# 04pwr_pmic.net
KiCad netlist of a schematic drawn in Altium Designer
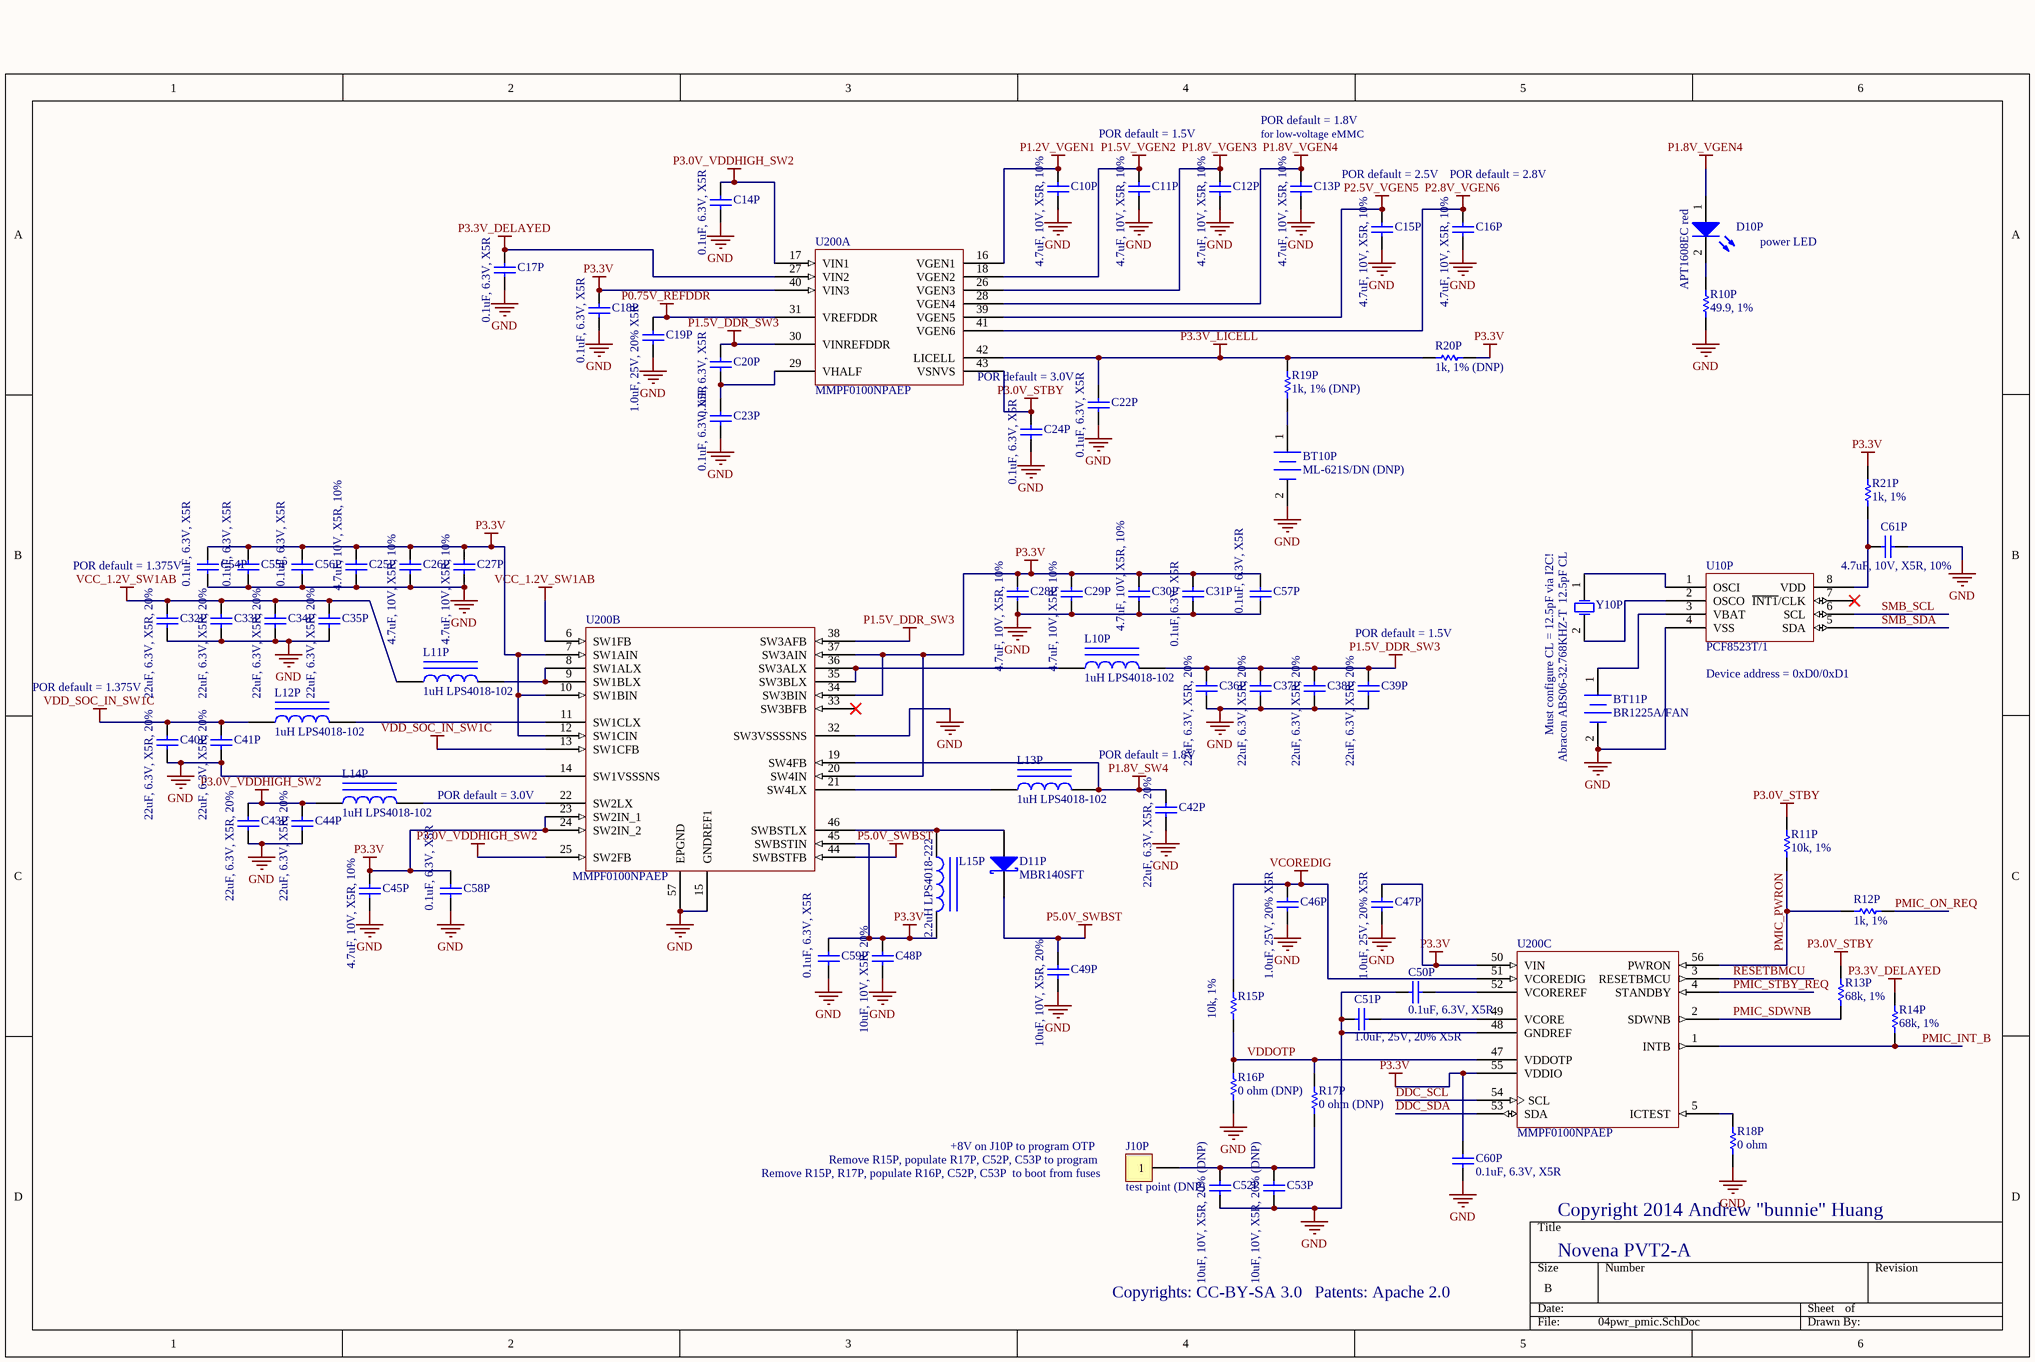
[diagram p0: 04pwr_pmic.SchDoc]

(export (version "E")
  (design (tool "Eeschema 10.0.6"))
  (components
    (comp (ref "BT10P")
      (value "ML-621S/DN (DNP)")
      (footprint "PAN_ML-621S-DN")
      (description "Panasonic Manganese Lithium Rechargeable battery")
      (fields (field (name "PUBLISHER") "Altium Limited"))
      (libsource (lib "Miscellaneous Devices") (part "Battery"))
    )
    (comp (ref "BT11P")
      (value "BR1225A/FAN")
      (footprint "BR1225A/FA")
      (description "Panasonic Manganese Lithium Rechargeable battery")
      (fields (field (name "PUBLISHER") "Altium Limited"))
      (libsource (lib "Miscellaneous Devices") (part "Battery"))
    )
    (comp (ref "C10P")
      (value "4.7uF, 10V, X5R, 10%")
      (footprint "CAPC1608N_HD")
      (description "Capacitor (Semiconductor SIM Model)")
      (fields (field (name "PUBLISHER") "Altium Limited"))
      (libsource (lib "Miscellaneous Devices") (part "Cap Semi"))
    )
    (comp (ref "C11P")
      (value "4.7uF, 10V, X5R, 10%")
      (footprint "CAPC1608N_HD")
      (description "Capacitor (Semiconductor SIM Model)")
      (fields (field (name "PUBLISHER") "Altium Limited"))
      (libsource (lib "Miscellaneous Devices") (part "Cap Semi"))
    )
    (comp (ref "C12P")
      (value "4.7uF, 10V, X5R, 10%")
      (footprint "CAPC1608N_HD")
      (description "Capacitor (Semiconductor SIM Model)")
      (fields (field (name "PUBLISHER") "Altium Limited"))
      (libsource (lib "Miscellaneous Devices") (part "Cap Semi"))
    )
    (comp (ref "C13P")
      (value "4.7uF, 10V, X5R, 10%")
      (footprint "CAPC1608N_HD")
      (description "Capacitor (Semiconductor SIM Model)")
      (fields (field (name "PUBLISHER") "Altium Limited"))
      (libsource (lib "Miscellaneous Devices") (part "Cap Semi"))
    )
    (comp (ref "C14P")
      (value "0.1uF, 6.3V, X5R")
      (footprint "CAPC0603N_B")
      (description "Capacitor (Semiconductor SIM Model)")
      (fields (field (name "PUBLISHER") "Altium Limited"))
      (libsource (lib "Miscellaneous Devices") (part "Cap Semi"))
    )
    (comp (ref "C15P")
      (value "4.7uF, 10V, X5R, 10%")
      (footprint "CAPC1608N_HD")
      (description "Capacitor (Semiconductor SIM Model)")
      (fields (field (name "PUBLISHER") "Altium Limited"))
      (libsource (lib "Miscellaneous Devices") (part "Cap Semi"))
    )
    (comp (ref "C16P")
      (value "4.7uF, 10V, X5R, 10%")
      (footprint "CAPC1608N_HD")
      (description "Capacitor (Semiconductor SIM Model)")
      (fields (field (name "PUBLISHER") "Altium Limited"))
      (libsource (lib "Miscellaneous Devices") (part "Cap Semi"))
    )
    (comp (ref "C17P")
      (value "0.1uF, 6.3V, X5R")
      (footprint "CAPC0603N_B")
      (description "Capacitor (Semiconductor SIM Model)")
      (fields (field (name "PUBLISHER") "Altium Limited"))
      (libsource (lib "Miscellaneous Devices") (part "Cap Semi"))
    )
    (comp (ref "C18P")
      (value "0.1uF, 6.3V, X5R")
      (footprint "CAPC0603N_B")
      (description "Capacitor (Semiconductor SIM Model)")
      (fields (field (name "PUBLISHER") "Altium Limited"))
      (libsource (lib "Miscellaneous Devices") (part "Cap Semi"))
    )
    (comp (ref "C19P")
      (value "1.0uF, 25V, 20% X5R")
      (footprint "CAPC1608N_HD")
      (description "Capacitor (Semiconductor SIM Model)")
      (fields (field (name "PUBLISHER") "Altium Limited"))
      (libsource (lib "Miscellaneous Devices") (part "Cap Semi"))
    )
    (comp (ref "C20P")
      (value "0.1uF, 6.3V, X5R")
      (footprint "CAPC0603N_B")
      (description "Capacitor (Semiconductor SIM Model)")
      (fields (field (name "PUBLISHER") "Altium Limited"))
      (libsource (lib "Miscellaneous Devices") (part "Cap Semi"))
    )
    (comp (ref "C22P")
      (value "0.1uF, 6.3V, X5R")
      (footprint "CAPC0603N_B")
      (description "Capacitor (Semiconductor SIM Model)")
      (fields (field (name "PUBLISHER") "Altium Limited"))
      (libsource (lib "Miscellaneous Devices") (part "Cap Semi"))
    )
    (comp (ref "C23P")
      (value "0.1uF, 6.3V, X5R")
      (footprint "CAPC0603N_B")
      (description "Capacitor (Semiconductor SIM Model)")
      (fields (field (name "PUBLISHER") "Altium Limited"))
      (libsource (lib "Miscellaneous Devices") (part "Cap Semi"))
    )
    (comp (ref "C24P")
      (value "0.1uF, 6.3V, X5R")
      (footprint "CAPC0603N_B")
      (description "Capacitor (Semiconductor SIM Model)")
      (fields (field (name "PUBLISHER") "Altium Limited"))
      (libsource (lib "Miscellaneous Devices") (part "Cap Semi"))
    )
    (comp (ref "C25P")
      (value "4.7uF, 10V, X5R, 10%")
      (footprint "CAPC1608N_HD")
      (description "Capacitor (Semiconductor SIM Model)")
      (fields (field (name "PUBLISHER") "Altium Limited"))
      (libsource (lib "Miscellaneous Devices") (part "Cap Semi"))
    )
    (comp (ref "C26P")
      (value "4.7uF, 10V, X5R, 10%")
      (footprint "CAPC1608N_HD")
      (description "Capacitor (Semiconductor SIM Model)")
      (fields (field (name "PUBLISHER") "Altium Limited"))
      (libsource (lib "Miscellaneous Devices") (part "Cap Semi"))
    )
    (comp (ref "C27P")
      (value "4.7uF, 10V, X5R, 10%")
      (footprint "CAPC1608N_HD")
      (description "Capacitor (Semiconductor SIM Model)")
      (fields (field (name "PUBLISHER") "Altium Limited"))
      (libsource (lib "Miscellaneous Devices") (part "Cap Semi"))
    )
    (comp (ref "C28P")
      (value "4.7uF, 10V, X5R, 10%")
      (footprint "CAPC1608N_HD")
      (description "Capacitor (Semiconductor SIM Model)")
      (fields (field (name "PUBLISHER") "Altium Limited"))
      (libsource (lib "Miscellaneous Devices") (part "Cap Semi"))
    )
    (comp (ref "C29P")
      (value "4.7uF, 10V, X5R, 10%")
      (footprint "CAPC1608N_HD")
      (description "Capacitor (Semiconductor SIM Model)")
      (fields (field (name "PUBLISHER") "Altium Limited"))
      (libsource (lib "Miscellaneous Devices") (part "Cap Semi"))
    )
    (comp (ref "C30P")
      (value "4.7uF, 10V, X5R, 10%")
      (footprint "CAPC1608N_HD")
      (description "Capacitor (Semiconductor SIM Model)")
      (fields (field (name "PUBLISHER") "Altium Limited"))
      (libsource (lib "Miscellaneous Devices") (part "Cap Semi"))
    )
    (comp (ref "C31P")
      (value "0.1uF, 6.3V, X5R")
      (footprint "CAPC0603N_B")
      (description "Capacitor (Semiconductor SIM Model)")
      (fields (field (name "PUBLISHER") "Altium Limited"))
      (libsource (lib "Miscellaneous Devices") (part "Cap Semi"))
    )
    (comp (ref "C32P")
      (value "22uF, 6.3V, X5R, 20%")
      (footprint "CAPC1608N_HD")
      (description "Capacitor (Semiconductor SIM Model)")
      (fields (field (name "PUBLISHER") "Altium Limited"))
      (libsource (lib "Miscellaneous Devices") (part "Cap Semi"))
    )
    (comp (ref "C33P")
      (value "22uF, 6.3V, X5R, 20%")
      (footprint "CAPC1608N_HD")
      (description "Capacitor (Semiconductor SIM Model)")
      (fields (field (name "PUBLISHER") "Altium Limited"))
      (libsource (lib "Miscellaneous Devices") (part "Cap Semi"))
    )
    (comp (ref "C34P")
      (value "22uF, 6.3V, X5R, 20%")
      (footprint "CAPC1608N_HD")
      (description "Capacitor (Semiconductor SIM Model)")
      (fields (field (name "PUBLISHER") "Altium Limited"))
      (libsource (lib "Miscellaneous Devices") (part "Cap Semi"))
    )
    (comp (ref "C35P")
      (value "22uF, 6.3V, X5R, 20%")
      (footprint "CAPC1608N_HD")
      (description "Capacitor (Semiconductor SIM Model)")
      (fields (field (name "PUBLISHER") "Altium Limited"))
      (libsource (lib "Miscellaneous Devices") (part "Cap Semi"))
    )
    (comp (ref "C36P")
      (value "22uF, 6.3V, X5R, 20%")
      (footprint "CAPC1608N_HD")
      (description "Capacitor (Semiconductor SIM Model)")
      (fields (field (name "PUBLISHER") "Altium Limited"))
      (libsource (lib "Miscellaneous Devices") (part "Cap Semi"))
    )
    (comp (ref "C37P")
      (value "22uF, 6.3V, X5R, 20%")
      (footprint "CAPC1608N_HD")
      (description "Capacitor (Semiconductor SIM Model)")
      (fields (field (name "PUBLISHER") "Altium Limited"))
      (libsource (lib "Miscellaneous Devices") (part "Cap Semi"))
    )
    (comp (ref "C38P")
      (value "22uF, 6.3V, X5R, 20%")
      (footprint "CAPC1608N_HD")
      (description "Capacitor (Semiconductor SIM Model)")
      (fields (field (name "PUBLISHER") "Altium Limited"))
      (libsource (lib "Miscellaneous Devices") (part "Cap Semi"))
    )
    (comp (ref "C39P")
      (value "22uF, 6.3V, X5R, 20%")
      (footprint "CAPC1608N_HD")
      (description "Capacitor (Semiconductor SIM Model)")
      (fields (field (name "PUBLISHER") "Altium Limited"))
      (libsource (lib "Miscellaneous Devices") (part "Cap Semi"))
    )
    (comp (ref "C40P")
      (value "22uF, 6.3V, X5R, 20%")
      (footprint "CAPC1608N_HD")
      (description "Capacitor (Semiconductor SIM Model)")
      (fields (field (name "PUBLISHER") "Altium Limited"))
      (libsource (lib "Miscellaneous Devices") (part "Cap Semi"))
    )
    (comp (ref "C41P")
      (value "22uF, 6.3V, X5R, 20%")
      (footprint "CAPC1608N_HD")
      (description "Capacitor (Semiconductor SIM Model)")
      (fields (field (name "PUBLISHER") "Altium Limited"))
      (libsource (lib "Miscellaneous Devices") (part "Cap Semi"))
    )
    (comp (ref "C42P")
      (value "22uF, 6.3V, X5R, 20%")
      (footprint "CAPC1608N_HD")
      (description "Capacitor (Semiconductor SIM Model)")
      (fields (field (name "PUBLISHER") "Altium Limited"))
      (libsource (lib "Miscellaneous Devices") (part "Cap Semi"))
    )
    (comp (ref "C43P")
      (value "22uF, 6.3V, X5R, 20%")
      (footprint "CAPC1608N_HD")
      (description "Capacitor (Semiconductor SIM Model)")
      (fields (field (name "PUBLISHER") "Altium Limited"))
      (libsource (lib "Miscellaneous Devices") (part "Cap Semi"))
    )
    (comp (ref "C44P")
      (value "22uF, 6.3V, X5R, 20%")
      (footprint "CAPC1608N_HD")
      (description "Capacitor (Semiconductor SIM Model)")
      (fields (field (name "PUBLISHER") "Altium Limited"))
      (libsource (lib "Miscellaneous Devices") (part "Cap Semi"))
    )
    (comp (ref "C45P")
      (value "4.7uF, 10V, X5R, 10%")
      (footprint "CAPC1608N_HD")
      (description "Capacitor (Semiconductor SIM Model)")
      (fields (field (name "PUBLISHER") "Altium Limited"))
      (libsource (lib "Miscellaneous Devices") (part "Cap Semi"))
    )
    (comp (ref "C46P")
      (value "1.0uF, 25V, 20% X5R")
      (footprint "CAPC1608N_HD")
      (description "Capacitor (Semiconductor SIM Model)")
      (fields (field (name "PUBLISHER") "Altium Limited"))
      (libsource (lib "Miscellaneous Devices") (part "Cap Semi"))
    )
    (comp (ref "C47P")
      (value "1.0uF, 25V, 20% X5R")
      (footprint "CAPC1608N_HD")
      (description "Capacitor (Semiconductor SIM Model)")
      (fields (field (name "PUBLISHER") "Altium Limited"))
      (libsource (lib "Miscellaneous Devices") (part "Cap Semi"))
    )
    (comp (ref "C48P")
      (value "10uF, 10V, X5R, 20%")
      (footprint "CAPC1608N")
      (description "Capacitor (Semiconductor SIM Model)")
      (fields (field (name "PUBLISHER") "Altium Limited"))
      (libsource (lib "Miscellaneous Devices") (part "Cap Semi"))
    )
    (comp (ref "C49P")
      (value "10uF, 10V, X5R, 20%")
      (footprint "CAPC1608N")
      (description "Capacitor (Semiconductor SIM Model)")
      (fields (field (name "PUBLISHER") "Altium Limited"))
      (libsource (lib "Miscellaneous Devices") (part "Cap Semi"))
    )
    (comp (ref "C50P")
      (value "0.1uF, 6.3V, X5R")
      (footprint "CAPC0603N_B")
      (description "Capacitor (Semiconductor SIM Model)")
      (fields (field (name "PUBLISHER") "Altium Limited"))
      (libsource (lib "Miscellaneous Devices") (part "Cap Semi"))
    )
    (comp (ref "C51P")
      (value "1.0uF, 25V, 20% X5R")
      (footprint "CAPC1608N_HD")
      (description "Capacitor (Semiconductor SIM Model)")
      (fields (field (name "PUBLISHER") "Altium Limited"))
      (libsource (lib "Miscellaneous Devices") (part "Cap Semi"))
    )
    (comp (ref "C52P")
      (value "10uF, 10V, X5R, 20% (DNP)")
      (footprint "CAPC1608N")
      (description "Capacitor (Semiconductor SIM Model)")
      (fields (field (name "PUBLISHER") "Altium Limited"))
      (libsource (lib "Miscellaneous Devices") (part "Cap Semi"))
    )
    (comp (ref "C53P")
      (value "10uF, 10V, X5R, 20% (DNP)")
      (footprint "CAPC1608N")
      (description "Capacitor (Semiconductor SIM Model)")
      (fields (field (name "PUBLISHER") "Altium Limited"))
      (libsource (lib "Miscellaneous Devices") (part "Cap Semi"))
    )
    (comp (ref "C54P")
      (value "0.1uF, 6.3V, X5R")
      (footprint "CAPC0603N_B")
      (description "Capacitor (Semiconductor SIM Model)")
      (fields (field (name "PUBLISHER") "Altium Limited"))
      (libsource (lib "Miscellaneous Devices") (part "Cap Semi"))
    )
    (comp (ref "C55P")
      (value "0.1uF, 6.3V, X5R")
      (footprint "CAPC0603N_B")
      (description "Capacitor (Semiconductor SIM Model)")
      (fields (field (name "PUBLISHER") "Altium Limited"))
      (libsource (lib "Miscellaneous Devices") (part "Cap Semi"))
    )
    (comp (ref "C56P")
      (value "0.1uF, 6.3V, X5R")
      (footprint "CAPC0603N_B")
      (description "Capacitor (Semiconductor SIM Model)")
      (fields (field (name "PUBLISHER") "Altium Limited"))
      (libsource (lib "Miscellaneous Devices") (part "Cap Semi"))
    )
    (comp (ref "C57P")
      (value "0.1uF, 6.3V, X5R")
      (footprint "CAPC0603N_B")
      (description "Capacitor (Semiconductor SIM Model)")
      (fields (field (name "PUBLISHER") "Altium Limited"))
      (libsource (lib "Miscellaneous Devices") (part "Cap Semi"))
    )
    (comp (ref "C58P")
      (value "0.1uF, 6.3V, X5R")
      (footprint "CAPC0603N_B")
      (description "Capacitor (Semiconductor SIM Model)")
      (fields (field (name "PUBLISHER") "Altium Limited"))
      (libsource (lib "Miscellaneous Devices") (part "Cap Semi"))
    )
    (comp (ref "C59P")
      (value "0.1uF, 6.3V, X5R")
      (footprint "CAPC0603N_B")
      (description "Capacitor (Semiconductor SIM Model)")
      (fields (field (name "PUBLISHER") "Altium Limited"))
      (libsource (lib "Miscellaneous Devices") (part "Cap Semi"))
    )
    (comp (ref "C60P")
      (value "0.1uF, 6.3V, X5R")
      (footprint "CAPC0603N_B")
      (description "Capacitor (Semiconductor SIM Model)")
      (fields (field (name "PUBLISHER") "Altium Limited"))
      (libsource (lib "Miscellaneous Devices") (part "Cap Semi"))
    )
    (comp (ref "C61P")
      (value "4.7uF, 10V, X5R, 10%")
      (footprint "CAPC1608N_HD")
      (description "Capacitor (Semiconductor SIM Model)")
      (fields (field (name "PUBLISHER") "Altium Limited"))
      (libsource (lib "Miscellaneous Devices") (part "Cap Semi"))
    )
    (comp (ref "D10P")
      (value "APT1608EC red")
      (footprint "CD1608-0603")
      (description "Typical RED, GREEN, YELLOW, AMBER GaAs LED")
      (fields (field (name "PUBLISHER") "Altium Limited"))
      (libsource (lib "Miscellaneous Devices") (part "LED2"))
    )
    (comp (ref "D11P")
      (value "MBR140SFT")
      (footprint "SOD123")
      (description "Schottky Diode")
      (fields (field (name "PUBLISHER") "Altium Limited"))
      (libsource (lib "Miscellaneous Devices") (part "D Schottky"))
    )
    (comp (ref "J10P")
      (value "test point (DNP)")
      (footprint "TP_SMT_38mil")
      (description "Connector")
      (libsource (lib "*") (part "CON1"))
    )
    (comp (ref "L10P")
      (value "1uH LPS4018-102")
      (footprint "COILCRAFT_LPS4018")
      (description "Magnetic-Core Inductor")
      (fields (field (name "PUBLISHER") "Altium Limited"))
      (libsource (lib "Miscellaneous Devices") (part "Inductor Iron"))
    )
    (comp (ref "L11P")
      (value "1uH LPS4018-102")
      (footprint "COILCRAFT_LPS4018")
      (description "Magnetic-Core Inductor")
      (fields (field (name "PUBLISHER") "Altium Limited"))
      (libsource (lib "Miscellaneous Devices") (part "Inductor Iron"))
    )
    (comp (ref "L12P")
      (value "1uH LPS4018-102")
      (footprint "COILCRAFT_LPS4018")
      (description "Magnetic-Core Inductor")
      (fields (field (name "PUBLISHER") "Altium Limited"))
      (libsource (lib "Miscellaneous Devices") (part "Inductor Iron"))
    )
    (comp (ref "L13P")
      (value "1uH LPS4018-102")
      (footprint "COILCRAFT_LPS4018")
      (description "Magnetic-Core Inductor")
      (fields (field (name "PUBLISHER") "Altium Limited"))
      (libsource (lib "Miscellaneous Devices") (part "Inductor Iron"))
    )
    (comp (ref "L14P")
      (value "1uH LPS4018-102")
      (footprint "COILCRAFT_LPS4018")
      (description "Magnetic-Core Inductor")
      (fields (field (name "PUBLISHER") "Altium Limited"))
      (libsource (lib "Miscellaneous Devices") (part "Inductor Iron"))
    )
    (comp (ref "L15P")
      (value "2.2uH LPS4018-222")
      (footprint "COILCRAFT_LPS4018")
      (description "Magnetic-Core Inductor")
      (fields (field (name "PUBLISHER") "Altium Limited"))
      (libsource (lib "Miscellaneous Devices") (part "Inductor Iron"))
    )
    (comp (ref "R10P")
      (value "49.9, 1%")
      (footprint "RESC1005N")
      (description "Resistor")
      (fields (field (name "PUBLISHER") "Altium Limited"))
      (libsource (lib "Miscellaneous Devices") (part "Res1"))
    )
    (comp (ref "R11P")
      (value "10k, 1%")
      (footprint "RESC1005N")
      (description "Resistor")
      (fields (field (name "PUBLISHER") "Altium Limited"))
      (libsource (lib "Miscellaneous Devices") (part "Res1"))
    )
    (comp (ref "R12P")
      (value "1k, 1%")
      (footprint "RESC1005N")
      (description "Resistor")
      (fields (field (name "PUBLISHER") "Altium Limited"))
      (libsource (lib "Miscellaneous Devices") (part "Res1"))
    )
    (comp (ref "R13P")
      (value "68k, 1%")
      (footprint "RESC1005N")
      (description "Resistor")
      (fields (field (name "PUBLISHER") "Altium Limited"))
      (libsource (lib "Miscellaneous Devices") (part "Res1"))
    )
    (comp (ref "R14P")
      (value "68k, 1%")
      (footprint "RESC1005N")
      (description "Resistor")
      (fields (field (name "PUBLISHER") "Altium Limited"))
      (libsource (lib "Miscellaneous Devices") (part "Res1"))
    )
    (comp (ref "R15P")
      (value "10k, 1%")
      (footprint "RESC1005N")
      (description "Resistor")
      (fields (field (name "PUBLISHER") "Altium Limited"))
      (libsource (lib "Miscellaneous Devices") (part "Res1"))
    )
    (comp (ref "R16P")
      (value "0 ohm (DNP)")
      (footprint "RESC1005N")
      (description "Resistor")
      (fields (field (name "PUBLISHER") "Altium Limited"))
      (libsource (lib "Miscellaneous Devices") (part "Res1"))
    )
    (comp (ref "R17P")
      (value "0 ohm (DNP)")
      (footprint "RESC1005N")
      (description "Resistor")
      (fields (field (name "PUBLISHER") "Altium Limited"))
      (libsource (lib "Miscellaneous Devices") (part "Res1"))
    )
    (comp (ref "R18P")
      (value "0 ohm")
      (footprint "RESC1005N")
      (description "Resistor")
      (fields (field (name "PUBLISHER") "Altium Limited"))
      (libsource (lib "Miscellaneous Devices") (part "Res1"))
    )
    (comp (ref "R19P")
      (value "1k, 1% (DNP)")
      (footprint "RESC1005N")
      (description "Resistor")
      (fields (field (name "PUBLISHER") "Altium Limited"))
      (libsource (lib "Miscellaneous Devices") (part "Res1"))
    )
    (comp (ref "R20P")
      (value "1k, 1% (DNP)")
      (footprint "RESC1005N")
      (description "Resistor")
      (fields (field (name "PUBLISHER") "Altium Limited"))
      (libsource (lib "Miscellaneous Devices") (part "Res1"))
    )
    (comp (ref "R21P")
      (value "1k, 1%")
      (footprint "RESC1005N")
      (description "Resistor")
      (fields (field (name "PUBLISHER") "Altium Limited"))
      (libsource (lib "Miscellaneous Devices") (part "Res1"))
    )
    (comp (ref "U10P")
      (value "PCF8523T/1")
      (footprint "SOIC127P600-8N")
      (description "RTC and calendar chip")
      (libsource (lib "commonsch") (part "PCF8523T/1"))
    )
    (comp (ref "U200")
      (value "MMPF0100NPAEP")
      (footprint "FREESCALE_QFN50P800X800X90-56N")
      (description "PMIC for i.MX6 series")
      (libsource (lib "commonsch") (part "PMPF0100NPEP"))
    )
    (comp (ref "Y10P")
      (value "Abracon ABS06-32.768KHZ-T  12.5pF CL")
      (footprint "ABS06")
      (description "Crystal Oscillator")
      (fields (field (name "PUBLISHER") "Altium Limited"))
      (libsource (lib "Miscellaneous Devices") (part "XTAL"))
    )
  )
  (nets
    (net (code "1") (name "/DDC_SCL") (class "Default")
      (node (ref "U200") (pin "54") (pinfunction "SCL_54") (pintype "input"))
    )
    (net (code "2") (name "/DDC_SDA") (class "Default")
      (node (ref "U200") (pin "53") (pinfunction "SDA_53") (pintype "bidirectional"))
    )
    (net (code "3") (name "/PMIC_INT_B") (class "Default")
      (node (ref "R14P") (pin "1") (pinfunction "1_1") (pintype "passive"))
      (node (ref "U200") (pin "1") (pinfunction "INTB_1") (pintype "output"))
    )
    (net (code "4") (name "/PMIC_ON_REQ") (class "Default")
      (node (ref "R12P") (pin "2") (pinfunction "2_2") (pintype "passive"))
    )
    (net (code "5") (name "/PMIC_PWRON") (class "Default")
      (node (ref "R11P") (pin "1") (pinfunction "1_1") (pintype "passive"))
      (node (ref "R12P") (pin "1") (pinfunction "1_1") (pintype "passive"))
      (node (ref "U200") (pin "56") (pinfunction "PWRON_56") (pintype "input"))
    )
    (net (code "6") (name "/PMIC_SDWNB") (class "Default")
      (node (ref "R13P") (pin "1") (pinfunction "1_1") (pintype "passive"))
      (node (ref "U200") (pin "2") (pinfunction "SDWNB_2") (pintype "output"))
    )
    (net (code "7") (name "/PMIC_STBY_REQ") (class "Default")
      (node (ref "U200") (pin "4") (pinfunction "STANDBY_4") (pintype "input"))
    )
    (net (code "8") (name "/RESETBMCU") (class "Default")
      (node (ref "U200") (pin "3") (pinfunction "RESETBMCU_3") (pintype "output"))
    )
    (net (code "9") (name "/SMB_SCL") (class "Default")
      (node (ref "U10P") (pin "6") (pinfunction "SCL_6") (pintype "bidirectional"))
    )
    (net (code "10") (name "/SMB_SDA") (class "Default")
      (node (ref "U10P") (pin "5") (pinfunction "SDA_5") (pintype "bidirectional"))
    )
    (net (code "11") (name "/VDDOTP") (class "Default")
      (node (ref "R15P") (pin "1") (pinfunction "1_1") (pintype "passive"))
      (node (ref "R16P") (pin "2") (pinfunction "2_2") (pintype "passive"))
      (node (ref "R17P") (pin "2") (pinfunction "2_2") (pintype "passive"))
      (node (ref "U200") (pin "47") (pinfunction "VDDOTP_47") (pintype "passive"))
    )
    (net (code "12") (name "GND") (class "Default")
      (node (ref "BT10P") (pin "2") (pinfunction "-_2") (pintype "passive"))
      (node (ref "BT11P") (pin "2") (pinfunction "-_2") (pintype "passive"))
      (node (ref "C10P") (pin "2") (pinfunction "2_2") (pintype "passive"))
      (node (ref "C11P") (pin "2") (pinfunction "2_2") (pintype "passive"))
      (node (ref "C12P") (pin "2") (pinfunction "2_2") (pintype "passive"))
      (node (ref "C13P") (pin "2") (pinfunction "2_2") (pintype "passive"))
      (node (ref "C14P") (pin "2") (pinfunction "2_2") (pintype "passive"))
      (node (ref "C15P") (pin "2") (pinfunction "2_2") (pintype "passive"))
      (node (ref "C16P") (pin "2") (pinfunction "2_2") (pintype "passive"))
      (node (ref "C17P") (pin "2") (pinfunction "2_2") (pintype "passive"))
      (node (ref "C18P") (pin "2") (pinfunction "2_2") (pintype "passive"))
      (node (ref "C19P") (pin "2") (pinfunction "2_2") (pintype "passive"))
      (node (ref "C22P") (pin "2") (pinfunction "2_2") (pintype "passive"))
      (node (ref "C23P") (pin "2") (pinfunction "2_2") (pintype "passive"))
      (node (ref "C24P") (pin "2") (pinfunction "2_2") (pintype "passive"))
      (node (ref "C25P") (pin "2") (pinfunction "2_2") (pintype "passive"))
      (node (ref "C26P") (pin "2") (pinfunction "2_2") (pintype "passive"))
      (node (ref "C27P") (pin "2") (pinfunction "2_2") (pintype "passive"))
      (node (ref "C28P") (pin "2") (pinfunction "2_2") (pintype "passive"))
      (node (ref "C29P") (pin "2") (pinfunction "2_2") (pintype "passive"))
      (node (ref "C30P") (pin "2") (pinfunction "2_2") (pintype "passive"))
      (node (ref "C31P") (pin "2") (pinfunction "2_2") (pintype "passive"))
      (node (ref "C32P") (pin "2") (pinfunction "2_2") (pintype "passive"))
      (node (ref "C33P") (pin "2") (pinfunction "2_2") (pintype "passive"))
      (node (ref "C34P") (pin "2") (pinfunction "2_2") (pintype "passive"))
      (node (ref "C35P") (pin "2") (pinfunction "2_2") (pintype "passive"))
      (node (ref "C36P") (pin "2") (pinfunction "2_2") (pintype "passive"))
      (node (ref "C37P") (pin "2") (pinfunction "2_2") (pintype "passive"))
      (node (ref "C38P") (pin "2") (pinfunction "2_2") (pintype "passive"))
      (node (ref "C39P") (pin "2") (pinfunction "2_2") (pintype "passive"))
      (node (ref "C40P") (pin "2") (pinfunction "2_2") (pintype "passive"))
      (node (ref "C41P") (pin "2") (pinfunction "2_2") (pintype "passive"))
      (node (ref "C42P") (pin "2") (pinfunction "2_2") (pintype "passive"))
      (node (ref "C43P") (pin "2") (pinfunction "2_2") (pintype "passive"))
      (node (ref "C44P") (pin "2") (pinfunction "2_2") (pintype "passive"))
      (node (ref "C45P") (pin "2") (pinfunction "2_2") (pintype "passive"))
      (node (ref "C46P") (pin "2") (pinfunction "2_2") (pintype "passive"))
      (node (ref "C47P") (pin "2") (pinfunction "2_2") (pintype "passive"))
      (node (ref "C48P") (pin "2") (pinfunction "2_2") (pintype "passive"))
      (node (ref "C49P") (pin "2") (pinfunction "2_2") (pintype "passive"))
      (node (ref "C50P") (pin "2") (pinfunction "2_2") (pintype "passive"))
      (node (ref "C51P") (pin "2") (pinfunction "2_2") (pintype "passive"))
      (node (ref "C52P") (pin "2") (pinfunction "2_2") (pintype "passive"))
      (node (ref "C53P") (pin "2") (pinfunction "2_2") (pintype "passive"))
      (node (ref "C54P") (pin "2") (pinfunction "2_2") (pintype "passive"))
      (node (ref "C55P") (pin "2") (pinfunction "2_2") (pintype "passive"))
      (node (ref "C56P") (pin "2") (pinfunction "2_2") (pintype "passive"))
      (node (ref "C57P") (pin "2") (pinfunction "2_2") (pintype "passive"))
      (node (ref "C58P") (pin "2") (pinfunction "2_2") (pintype "passive"))
      (node (ref "C59P") (pin "2") (pinfunction "2_2") (pintype "passive"))
      (node (ref "C60P") (pin "1") (pinfunction "1_1") (pintype "passive"))
      (node (ref "C61P") (pin "2") (pinfunction "2_2") (pintype "passive"))
      (node (ref "R10P") (pin "1") (pinfunction "1_1") (pintype "passive"))
      (node (ref "R16P") (pin "1") (pinfunction "1_1") (pintype "passive"))
      (node (ref "R18P") (pin "1") (pinfunction "1_1") (pintype "passive"))
      (node (ref "U10P") (pin "4") (pinfunction "VSS_4") (pintype "power_in"))
      (node (ref "U200") (pin "14") (pinfunction "SW1VSSSNS_14") (pintype "power_in"))
      (node (ref "U200") (pin "15") (pinfunction "GNDREF1_15") (pintype "power_in"))
      (node (ref "U200") (pin "32") (pinfunction "SW3VSSSSNS_32") (pintype "power_in"))
      (node (ref "U200") (pin "48") (pinfunction "GNDREF_48") (pintype "power_in"))
      (node (ref "U200") (pin "57") (pinfunction "EPGND_57") (pintype "power_in"))
    )
    (net (code "13") (name "Net-(BT10P-+)") (class "Default")
      (node (ref "BT10P") (pin "1") (pinfunction "+_1") (pintype "passive"))
      (node (ref "R19P") (pin "1") (pinfunction "1_1") (pintype "passive"))
    )
    (net (code "14") (name "Net-(BT11P-+)") (class "Default")
      (node (ref "BT11P") (pin "1") (pinfunction "+_1") (pintype "passive"))
      (node (ref "U10P") (pin "3") (pinfunction "VBAT_3") (pintype "power_in"))
    )
    (net (code "15") (name "Net-(C52P-Pad1)") (class "Default")
      (node (ref "C52P") (pin "1") (pinfunction "1_1") (pintype "passive"))
      (node (ref "C53P") (pin "1") (pinfunction "1_1") (pintype "passive"))
      (node (ref "J10P") (pin "1") (pinfunction "1_1") (pintype "passive"))
      (node (ref "R17P") (pin "1") (pinfunction "1_1") (pintype "passive"))
    )
    (net (code "16") (name "Net-(D10P-K)") (class "Default")
      (node (ref "D10P") (pin "2") (pinfunction "K_2") (pintype "passive"))
      (node (ref "R10P") (pin "2") (pinfunction "2_2") (pintype "passive"))
    )
    (net (code "17") (name "Net-(D11P-A)") (class "Default")
      (node (ref "D11P") (pin "1") (pinfunction "A_1") (pintype "passive"))
      (node (ref "L15P") (pin "1") (pinfunction "1_1") (pintype "passive"))
      (node (ref "U200") (pin "46") (pinfunction "SWBSTLX_46") (pintype "passive"))
    )
    (net (code "18") (name "Net-(U10P-OSCI)") (class "Default")
      (node (ref "U10P") (pin "1") (pinfunction "OSCI_1") (pintype "passive"))
      (node (ref "Y10P") (pin "1") (pinfunction "OSC1_1") (pintype "passive"))
    )
    (net (code "19") (name "Net-(U10P-OSCO)") (class "Default")
      (node (ref "U10P") (pin "2") (pinfunction "OSCO_2") (pintype "passive"))
      (node (ref "Y10P") (pin "2") (pinfunction "OSC2_2") (pintype "passive"))
    )
    (net (code "20") (name "Net-(U10P-VDD)") (class "Default")
      (node (ref "C61P") (pin "1") (pinfunction "1_1") (pintype "passive"))
      (node (ref "R21P") (pin "1") (pinfunction "1_1") (pintype "passive"))
      (node (ref "U10P") (pin "8") (pinfunction "VDD_8") (pintype "power_in"))
    )
    (net (code "21") (name "Net-(U200A-VHALF)") (class "Default")
      (node (ref "C20P") (pin "2") (pinfunction "2_2") (pintype "passive"))
      (node (ref "C23P") (pin "1") (pinfunction "1_1") (pintype "passive"))
      (node (ref "U200") (pin "29") (pinfunction "VHALF_29") (pintype "passive"))
    )
    (net (code "22") (name "Net-(U200B-SW1ALX)") (class "Default")
      (node (ref "L11P") (pin "2") (pinfunction "2_2") (pintype "passive"))
      (node (ref "U200") (pin "8") (pinfunction "SW1ALX_8") (pintype "passive"))
      (node (ref "U200") (pin "9") (pinfunction "SW1BLX_9") (pintype "passive"))
    )
    (net (code "23") (name "Net-(U200B-SW1CLX)") (class "Default")
      (node (ref "L12P") (pin "2") (pinfunction "2_2") (pintype "passive"))
      (node (ref "U200") (pin "11") (pinfunction "SW1CLX_11") (pintype "passive"))
    )
    (net (code "24") (name "Net-(U200B-SW2LX)") (class "Default")
      (node (ref "L14P") (pin "2") (pinfunction "2_2") (pintype "passive"))
      (node (ref "U200") (pin "22") (pinfunction "SW2LX_22") (pintype "passive"))
    )
    (net (code "25") (name "Net-(U200B-SW3ALX)") (class "Default")
      (node (ref "L10P") (pin "1") (pinfunction "1_1") (pintype "passive"))
      (node (ref "U200") (pin "35") (pinfunction "SW3BLX_35") (pintype "passive"))
      (node (ref "U200") (pin "36") (pinfunction "SW3ALX_36") (pintype "passive"))
    )
    (net (code "26") (name "Net-(U200B-SW4LX)") (class "Default")
      (node (ref "L13P") (pin "1") (pinfunction "1_1") (pintype "passive"))
      (node (ref "U200") (pin "21") (pinfunction "SW4LX_21") (pintype "passive"))
    )
    (net (code "27") (name "Net-(U200C-ICTEST)") (class "Default")
      (node (ref "R18P") (pin "2") (pinfunction "2_2") (pintype "passive"))
      (node (ref "U200") (pin "5") (pinfunction "ICTEST_5") (pintype "input"))
    )
    (net (code "28") (name "Net-(U200C-VCORE)") (class "Default")
      (node (ref "C51P") (pin "1") (pinfunction "1_1") (pintype "passive"))
      (node (ref "U200") (pin "49") (pinfunction "VCORE_49") (pintype "passive"))
    )
    (net (code "29") (name "Net-(U200C-VCOREREF)") (class "Default")
      (node (ref "C50P") (pin "1") (pinfunction "1_1") (pintype "passive"))
      (node (ref "U200") (pin "52") (pinfunction "VCOREREF_52") (pintype "passive"))
    )
    (net (code "30") (name "P0.75V_REFDDR") (class "Default")
      (node (ref "C19P") (pin "1") (pinfunction "1_1") (pintype "passive"))
      (node (ref "U200") (pin "31") (pinfunction "VREFDDR_31") (pintype "power_in"))
    )
    (net (code "31") (name "P1.2V_VGEN1") (class "Default")
      (node (ref "C10P") (pin "1") (pinfunction "1_1") (pintype "passive"))
      (node (ref "U200") (pin "16") (pinfunction "VGEN1_16") (pintype "power_in"))
    )
    (net (code "32") (name "P1.5V_DDR_SW3") (class "Default")
      (node (ref "C20P") (pin "1") (pinfunction "1_1") (pintype "passive"))
      (node (ref "C36P") (pin "1") (pinfunction "1_1") (pintype "passive"))
      (node (ref "C37P") (pin "1") (pinfunction "1_1") (pintype "passive"))
      (node (ref "C38P") (pin "1") (pinfunction "1_1") (pintype "passive"))
      (node (ref "C39P") (pin "1") (pinfunction "1_1") (pintype "passive"))
      (node (ref "L10P") (pin "2") (pinfunction "2_2") (pintype "passive"))
      (node (ref "U200") (pin "30") (pinfunction "VINREFDDR_30") (pintype "power_in"))
      (node (ref "U200") (pin "38") (pinfunction "SW3AFB_38") (pintype "input"))
    )
    (net (code "33") (name "P1.5V_VGEN2") (class "Default")
      (node (ref "C11P") (pin "1") (pinfunction "1_1") (pintype "passive"))
      (node (ref "U200") (pin "18") (pinfunction "VGEN2_18") (pintype "power_in"))
    )
    (net (code "34") (name "P1.8V_SW4") (class "Default")
      (node (ref "C42P") (pin "1") (pinfunction "1_1") (pintype "passive"))
      (node (ref "L13P") (pin "2") (pinfunction "2_2") (pintype "passive"))
      (node (ref "U200") (pin "19") (pinfunction "SW4FB_19") (pintype "input"))
    )
    (net (code "35") (name "P1.8V_VGEN3") (class "Default")
      (node (ref "C12P") (pin "1") (pinfunction "1_1") (pintype "passive"))
      (node (ref "U200") (pin "26") (pinfunction "VGEN3_26") (pintype "power_in"))
    )
    (net (code "36") (name "P1.8V_VGEN4") (class "Default")
      (node (ref "C13P") (pin "1") (pinfunction "1_1") (pintype "passive"))
      (node (ref "D10P") (pin "1") (pinfunction "A_1") (pintype "passive"))
      (node (ref "U200") (pin "28") (pinfunction "VGEN4_28") (pintype "power_in"))
    )
    (net (code "37") (name "P2.5V_VGEN5") (class "Default")
      (node (ref "C15P") (pin "1") (pinfunction "1_1") (pintype "passive"))
      (node (ref "U200") (pin "39") (pinfunction "VGEN5_39") (pintype "power_in"))
    )
    (net (code "38") (name "P2.8V_VGEN6") (class "Default")
      (node (ref "C16P") (pin "1") (pinfunction "1_1") (pintype "passive"))
      (node (ref "U200") (pin "41") (pinfunction "VGEN6_41") (pintype "power_in"))
    )
    (net (code "39") (name "P3.0V_STBY") (class "Default")
      (node (ref "C24P") (pin "1") (pinfunction "1_1") (pintype "passive"))
      (node (ref "R11P") (pin "2") (pinfunction "2_2") (pintype "passive"))
      (node (ref "R13P") (pin "2") (pinfunction "2_2") (pintype "passive"))
      (node (ref "U200") (pin "43") (pinfunction "VSNVS_43") (pintype "power_in"))
    )
    (net (code "40") (name "P3.0V_VDDHIGH_SW2") (class "Default")
      (node (ref "C14P") (pin "1") (pinfunction "1_1") (pintype "passive"))
      (node (ref "C43P") (pin "1") (pinfunction "1_1") (pintype "passive"))
      (node (ref "C44P") (pin "1") (pinfunction "1_1") (pintype "passive"))
      (node (ref "L14P") (pin "1") (pinfunction "1_1") (pintype "passive"))
      (node (ref "U200") (pin "17") (pinfunction "VIN1_17") (pintype "input"))
      (node (ref "U200") (pin "25") (pinfunction "SW2FB_25") (pintype "input"))
    )
    (net (code "41") (name "P3.3V") (class "Default")
      (node (ref "C18P") (pin "1") (pinfunction "1_1") (pintype "passive"))
      (node (ref "C25P") (pin "1") (pinfunction "1_1") (pintype "passive"))
      (node (ref "C26P") (pin "1") (pinfunction "1_1") (pintype "passive"))
      (node (ref "C27P") (pin "1") (pinfunction "1_1") (pintype "passive"))
      (node (ref "C28P") (pin "1") (pinfunction "1_1") (pintype "passive"))
      (node (ref "C29P") (pin "1") (pinfunction "1_1") (pintype "passive"))
      (node (ref "C30P") (pin "1") (pinfunction "1_1") (pintype "passive"))
      (node (ref "C31P") (pin "1") (pinfunction "1_1") (pintype "passive"))
      (node (ref "C45P") (pin "1") (pinfunction "1_1") (pintype "passive"))
      (node (ref "C47P") (pin "1") (pinfunction "1_1") (pintype "passive"))
      (node (ref "C48P") (pin "1") (pinfunction "1_1") (pintype "passive"))
      (node (ref "C54P") (pin "1") (pinfunction "1_1") (pintype "passive"))
      (node (ref "C55P") (pin "1") (pinfunction "1_1") (pintype "passive"))
      (node (ref "C56P") (pin "1") (pinfunction "1_1") (pintype "passive"))
      (node (ref "C57P") (pin "1") (pinfunction "1_1") (pintype "passive"))
      (node (ref "C58P") (pin "1") (pinfunction "1_1") (pintype "passive"))
      (node (ref "C59P") (pin "1") (pinfunction "1_1") (pintype "passive"))
      (node (ref "C60P") (pin "2") (pinfunction "2_2") (pintype "passive"))
      (node (ref "L15P") (pin "2") (pinfunction "2_2") (pintype "passive"))
      (node (ref "R20P") (pin "2") (pinfunction "2_2") (pintype "passive"))
      (node (ref "R21P") (pin "2") (pinfunction "2_2") (pintype "passive"))
      (node (ref "U200") (pin "10") (pinfunction "SW1BIN_10") (pintype "input"))
      (node (ref "U200") (pin "12") (pinfunction "SW1CIN_12") (pintype "input"))
      (node (ref "U200") (pin "20") (pinfunction "SW4IN_20") (pintype "input"))
      (node (ref "U200") (pin "23") (pinfunction "SW2IN_1_23") (pintype "input"))
      (node (ref "U200") (pin "24") (pinfunction "SW2IN_2_24") (pintype "input"))
      (node (ref "U200") (pin "34") (pinfunction "SW3BIN_34") (pintype "input"))
      (node (ref "U200") (pin "37") (pinfunction "SW3AIN_37") (pintype "input"))
      (node (ref "U200") (pin "40") (pinfunction "VIN3_40") (pintype "input"))
      (node (ref "U200") (pin "45") (pinfunction "SWBSTIN_45") (pintype "input"))
      (node (ref "U200") (pin "50") (pinfunction "VIN_50") (pintype "input"))
      (node (ref "U200") (pin "55") (pinfunction "VDDIO_55") (pintype "power_in"))
      (node (ref "U200") (pin "7") (pinfunction "SW1AIN_7") (pintype "input"))
    )
    (net (code "42") (name "P3.3V_DELAYED") (class "Default")
      (node (ref "C17P") (pin "1") (pinfunction "1_1") (pintype "passive"))
      (node (ref "R14P") (pin "2") (pinfunction "2_2") (pintype "passive"))
      (node (ref "U200") (pin "27") (pinfunction "VIN2_27") (pintype "input"))
    )
    (net (code "43") (name "P3.3V_LICELL") (class "Default")
      (node (ref "C22P") (pin "1") (pinfunction "1_1") (pintype "passive"))
      (node (ref "R19P") (pin "2") (pinfunction "2_2") (pintype "passive"))
      (node (ref "R20P") (pin "1") (pinfunction "1_1") (pintype "passive"))
      (node (ref "U200") (pin "42") (pinfunction "LICELL_42") (pintype "power_in"))
    )
    (net (code "44") (name "P5.0V_SWBST") (class "Default")
      (node (ref "C49P") (pin "1") (pinfunction "1_1") (pintype "passive"))
      (node (ref "D11P") (pin "2") (pinfunction "K_2") (pintype "passive"))
      (node (ref "U200") (pin "44") (pinfunction "SWBSTFB_44") (pintype "input"))
    )
    (net (code "45") (name "VCC_1.2V_SW1AB") (class "Default")
      (node (ref "C32P") (pin "1") (pinfunction "1_1") (pintype "passive"))
      (node (ref "C33P") (pin "1") (pinfunction "1_1") (pintype "passive"))
      (node (ref "C34P") (pin "1") (pinfunction "1_1") (pintype "passive"))
      (node (ref "C35P") (pin "1") (pinfunction "1_1") (pintype "passive"))
      (node (ref "L11P") (pin "1") (pinfunction "1_1") (pintype "passive"))
      (node (ref "U200") (pin "6") (pinfunction "SW1FB_6") (pintype "input"))
    )
    (net (code "46") (name "VCOREDIG") (class "Default")
      (node (ref "C46P") (pin "1") (pinfunction "1_1") (pintype "passive"))
      (node (ref "R15P") (pin "2") (pinfunction "2_2") (pintype "passive"))
      (node (ref "U200") (pin "51") (pinfunction "VCOREDIG_51") (pintype "input"))
    )
    (net (code "47") (name "VDD_SOC_IN_SW1C") (class "Default")
      (node (ref "C40P") (pin "1") (pinfunction "1_1") (pintype "passive"))
      (node (ref "C41P") (pin "1") (pinfunction "1_1") (pintype "passive"))
      (node (ref "L12P") (pin "1") (pinfunction "1_1") (pintype "passive"))
      (node (ref "U200") (pin "13") (pinfunction "SW1CFB_13") (pintype "input"))
    )
    (net (code "48") (name "unconnected-(U10P-~{INT1}{slash}CLK-Pad7)") (class "Default")
      (node (ref "U10P") (pin "7") (pinfunction "~{INT1}/CLK_7") (pintype "bidirectional+no_connect"))
    )
    (net (code "49") (name "unconnected-(U200B-SW3BFB-Pad33)") (class "Default")
      (node (ref "U200") (pin "33") (pinfunction "SW3BFB_33") (pintype "input+no_connect"))
    )
  )
)
